# CRDC.net
KiCad netlist of a schematic drawn in EAGLE
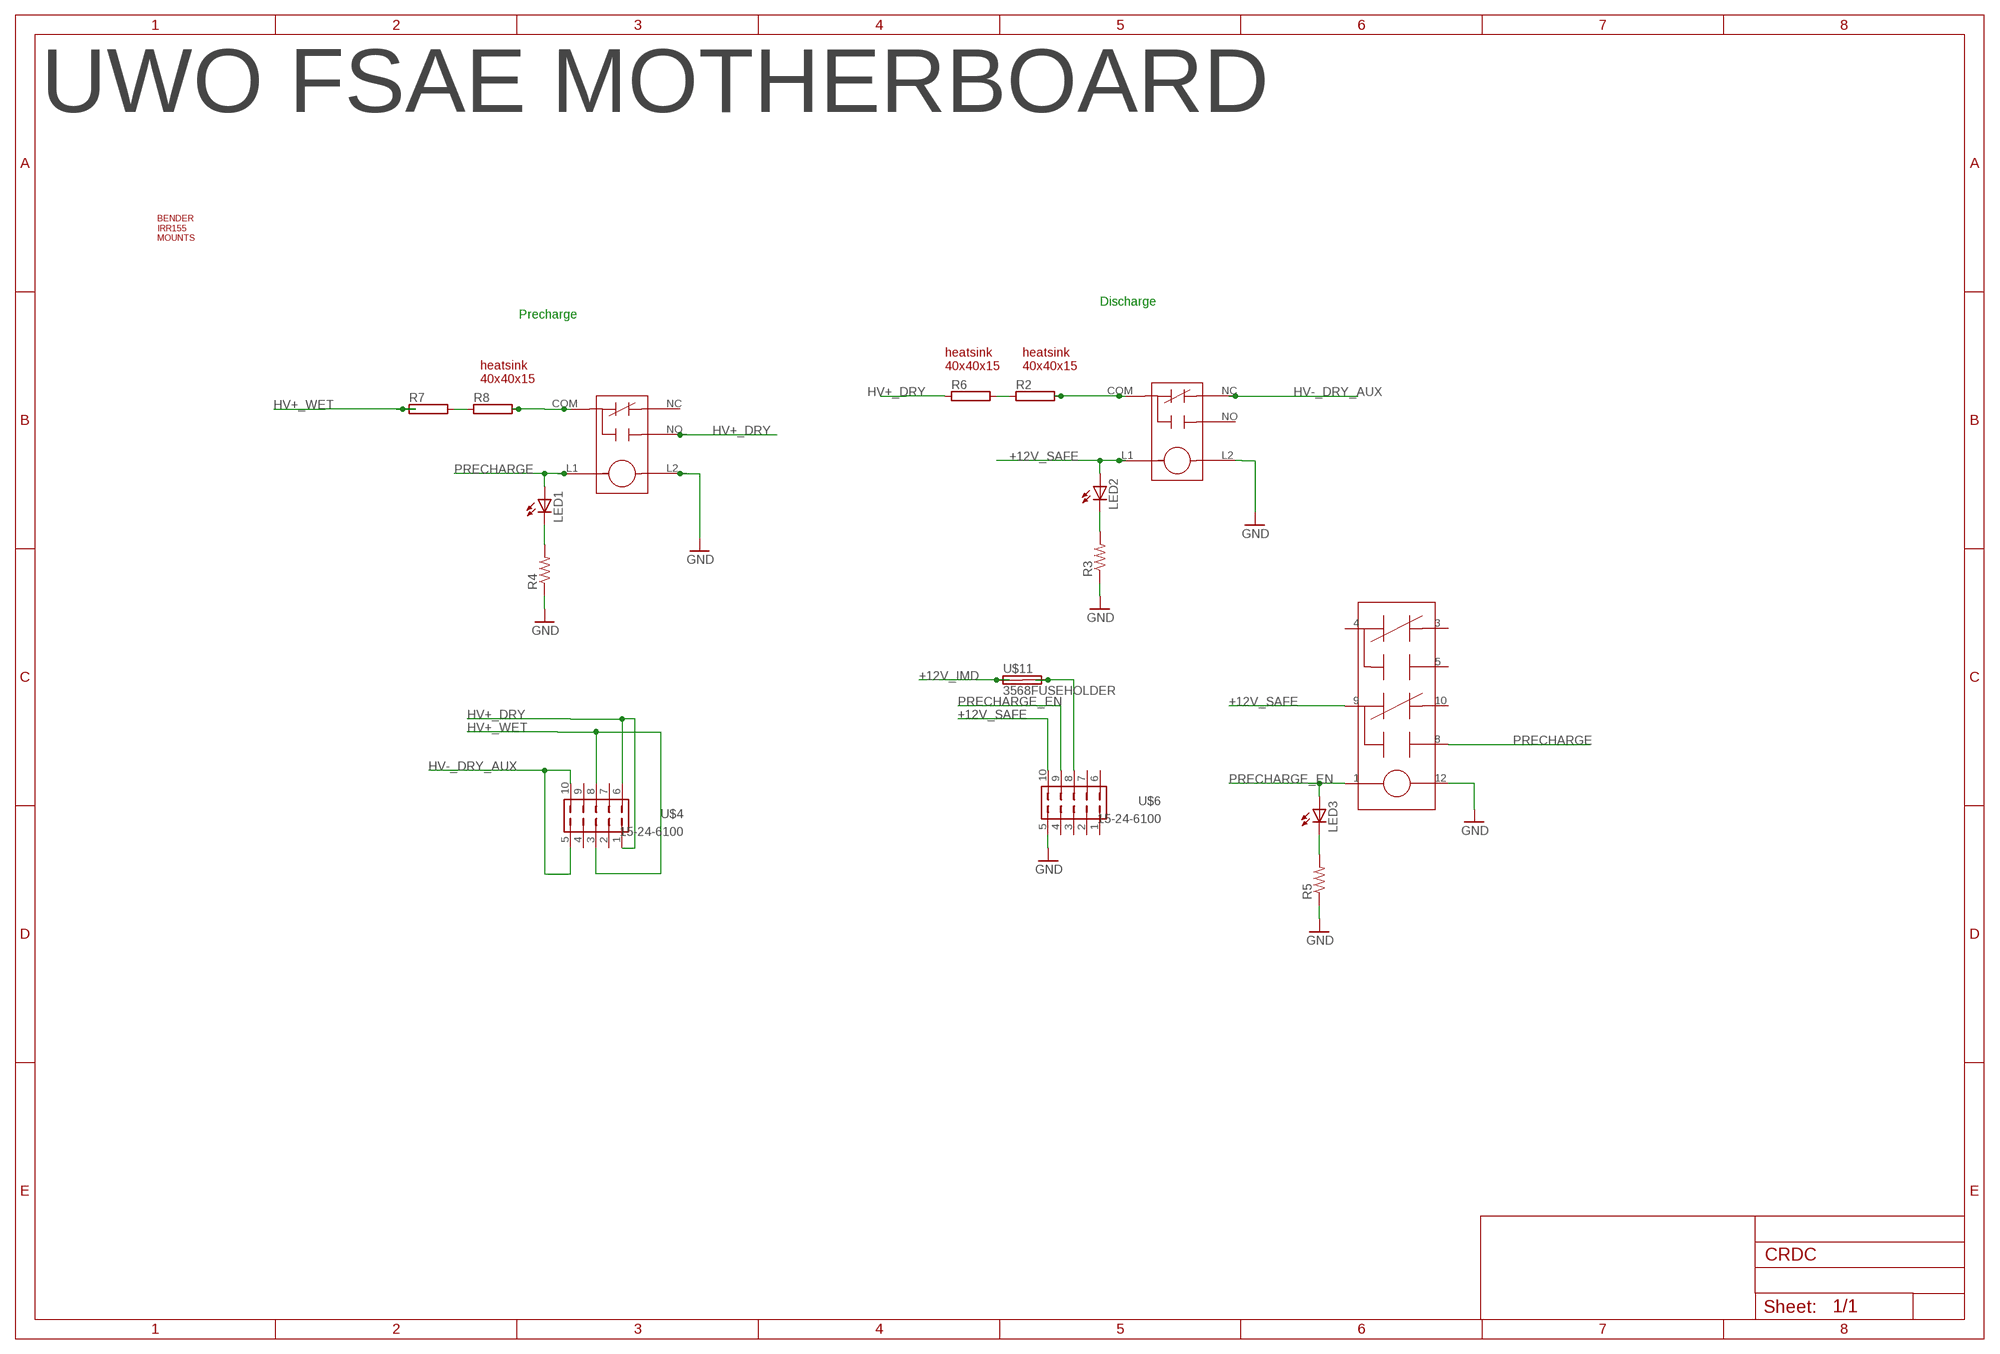
[diagram p0: schematic, sheet 1]

(export (version "E")
  (design (tool "Eeschema 10.0.6"))
  (components
    (comp (ref "LED1")
      (value "LED3MM")
      (footprint "eagle-import:LED3MM")
      (libsource (lib "eagle-import") (part "LED3MM"))
    )
    (comp (ref "LED2")
      (value "LED3MM")
      (footprint "eagle-import:LED3MM")
      (libsource (lib "eagle-import") (part "LED3MM"))
    )
    (comp (ref "LED3")
      (value "LED3MM")
      (footprint "eagle-import:LED3MM")
      (libsource (lib "eagle-import") (part "LED3MM"))
    )
    (comp (ref "R2")
      (value "RMG100-H")
      (footprint "eagle-import:TO-247-2H")
      (libsource (lib "eagle-import") (part "RMG100-H"))
    )
    (comp (ref "R3")
      (value "R-US_R0805")
      (footprint "eagle-import:R0805")
      (libsource (lib "eagle-import") (part "R-US_R0805"))
    )
    (comp (ref "R4")
      (value "R-US_R0805")
      (footprint "eagle-import:R0805")
      (libsource (lib "eagle-import") (part "R-US_R0805"))
    )
    (comp (ref "R5")
      (value "R-US_R0805")
      (footprint "eagle-import:R0805")
      (libsource (lib "eagle-import") (part "R-US_R0805"))
    )
    (comp (ref "R6")
      (value "RMG100-H")
      (footprint "eagle-import:TO-247-2H")
      (libsource (lib "eagle-import") (part "RMG100-H"))
    )
    (comp (ref "R7")
      (value "RMG100-H")
      (footprint "eagle-import:TO-247-2H")
      (libsource (lib "eagle-import") (part "RMG100-H"))
    )
    (comp (ref "R8")
      (value "RMG100-H")
      (footprint "eagle-import:TO-247-2H")
      (libsource (lib "eagle-import") (part "RMG100-H"))
    )
    (comp (ref "U$1")
      (value "G81C335")
      (footprint "eagle-import:G81C335")
      (libsource (lib "eagle-import") (part "G81C335"))
    )
    (comp (ref "U$2")
      (value "G81C335")
      (footprint "eagle-import:G81C335")
      (libsource (lib "eagle-import") (part "G81C335"))
    )
    (comp (ref "U$4")
      (value "15-24-6100")
      (footprint "eagle-import:15-24-6100")
      (libsource (lib "eagle-import") (part "15-24-6100"))
    )
    (comp (ref "U$5")
      (value "HEATSINK40X40X15")
      (footprint "eagle-import:HEATSINK40X40X15")
      (libsource (lib "eagle-import") (part "HEATSINK40X40X15"))
    )
    (comp (ref "U$6")
      (value "15-24-6100")
      (footprint "eagle-import:15-24-6100")
      (libsource (lib "eagle-import") (part "15-24-6100"))
    )
    (comp (ref "U$7")
      (value "V23079B1203B301")
      (footprint "eagle-import:V23079B1203B301")
      (libsource (lib "eagle-import") (part "V23079B1203B301"))
    )
    (comp (ref "U$8")
      (value "HEATSINK40X40X15")
      (footprint "eagle-import:HEATSINK40X40X15")
      (libsource (lib "eagle-import") (part "HEATSINK40X40X15"))
    )
    (comp (ref "U$9")
      (value "HEATSINK40X40X15")
      (footprint "eagle-import:HEATSINK40X40X15")
      (libsource (lib "eagle-import") (part "HEATSINK40X40X15"))
    )
    (comp (ref "U$10")
      (value "BENDER_IRR155")
      (footprint "eagle-import:BENDER_IRR155")
      (libsource (lib "eagle-import") (part "BENDER_IRR155"))
    )
    (comp (ref "U$11")
      (value "3568FUSEHOLDER")
      (footprint "eagle-import:3568")
      (libsource (lib "eagle-import") (part "3568FUSEHOLDER"))
    )
  )
  (nets
    (net (code "1") (name "/+12V_IMD") (class "Default")
      (node (ref "U$11") (pin "L1") (pinfunction "1A_L1") (pintype "passive"))
      (node (ref "U$11") (pin "L2") (pinfunction "1B_L2") (pintype "passive"))
    )
    (net (code "2") (name "/+12V_SAFE") (class "Default")
      (node (ref "LED2") (pin "A") (pinfunction "A_A") (pintype "passive"))
      (node (ref "U$2") (pin "L1") (pinfunction "L1_L1") (pintype "bidirectional"))
      (node (ref "U$6") (pin "10") (pinfunction "10_10") (pintype "passive"))
      (node (ref "U$7") (pin "9") (pinfunction "9_9") (pintype "bidirectional"))
    )
    (net (code "3") (name "/HV+_DRY") (class "Default")
      (node (ref "R6") (pin "1") (pinfunction "1_1") (pintype "passive"))
      (node (ref "U$1") (pin "NO") (pinfunction "NO_NO") (pintype "bidirectional"))
      (node (ref "U$4") (pin "1") (pinfunction "1_1") (pintype "passive"))
      (node (ref "U$4") (pin "6") (pinfunction "6_6") (pintype "passive"))
    )
    (net (code "4") (name "/HV+_WET") (class "Default")
      (node (ref "R7") (pin "1") (pinfunction "1_1") (pintype "passive"))
      (node (ref "U$4") (pin "3") (pinfunction "3_3") (pintype "passive"))
      (node (ref "U$4") (pin "8") (pinfunction "8_8") (pintype "passive"))
    )
    (net (code "5") (name "/HV-_DRY_AUX") (class "Default")
      (node (ref "U$2") (pin "NC") (pinfunction "NC_NC") (pintype "bidirectional"))
      (node (ref "U$4") (pin "10") (pinfunction "10_10") (pintype "passive"))
      (node (ref "U$4") (pin "5") (pinfunction "5_5") (pintype "passive"))
    )
    (net (code "6") (name "/PRECHARGE") (class "Default")
      (node (ref "LED1") (pin "A") (pinfunction "A_A") (pintype "passive"))
      (node (ref "U$1") (pin "L1") (pinfunction "L1_L1") (pintype "bidirectional"))
      (node (ref "U$7") (pin "8") (pinfunction "8_8") (pintype "bidirectional"))
    )
    (net (code "7") (name "/PRECHARGE_EN") (class "Default")
      (node (ref "LED3") (pin "A") (pinfunction "A_A") (pintype "passive"))
      (node (ref "U$6") (pin "9") (pinfunction "9_9") (pintype "passive"))
      (node (ref "U$7") (pin "1") (pinfunction "1_1") (pintype "bidirectional"))
    )
    (net (code "8") (name "GND") (class "Default")
      (node (ref "R3") (pin "1") (pinfunction "1_1") (pintype "passive"))
      (node (ref "R4") (pin "1") (pinfunction "1_1") (pintype "passive"))
      (node (ref "R5") (pin "1") (pinfunction "1_1") (pintype "passive"))
      (node (ref "U$1") (pin "L2") (pinfunction "L2_L2") (pintype "bidirectional"))
      (node (ref "U$2") (pin "L2") (pinfunction "L2_L2") (pintype "bidirectional"))
      (node (ref "U$6") (pin "5") (pinfunction "5_5") (pintype "passive"))
      (node (ref "U$7") (pin "12") (pinfunction "12_12") (pintype "bidirectional"))
    )
    (net (code "9") (name "Net-(LED1-C)") (class "Default")
      (node (ref "LED1") (pin "K") (pinfunction "C_K") (pintype "passive"))
      (node (ref "R4") (pin "2") (pinfunction "2_2") (pintype "passive"))
    )
    (net (code "10") (name "Net-(LED2-C)") (class "Default")
      (node (ref "LED2") (pin "K") (pinfunction "C_K") (pintype "passive"))
      (node (ref "R3") (pin "2") (pinfunction "2_2") (pintype "passive"))
    )
    (net (code "11") (name "Net-(LED3-C)") (class "Default")
      (node (ref "LED3") (pin "K") (pinfunction "C_K") (pintype "passive"))
      (node (ref "R5") (pin "2") (pinfunction "2_2") (pintype "passive"))
    )
    (net (code "12") (name "Net-(R2-Pad1)") (class "Default")
      (node (ref "R2") (pin "1") (pinfunction "1_1") (pintype "passive"))
      (node (ref "R6") (pin "2") (pinfunction "2_2") (pintype "passive"))
    )
    (net (code "13") (name "Net-(R2-Pad2)") (class "Default")
      (node (ref "R2") (pin "2") (pinfunction "2_2") (pintype "passive"))
      (node (ref "U$2") (pin "COM") (pinfunction "COM_COM") (pintype "bidirectional"))
    )
    (net (code "14") (name "Net-(R7-Pad2)") (class "Default")
      (node (ref "R7") (pin "2") (pinfunction "2_2") (pintype "passive"))
      (node (ref "R8") (pin "1") (pinfunction "1_1") (pintype "passive"))
    )
    (net (code "15") (name "Net-(R8-Pad2)") (class "Default")
      (node (ref "R8") (pin "2") (pinfunction "2_2") (pintype "passive"))
      (node (ref "U$1") (pin "COM") (pinfunction "COM_COM") (pintype "bidirectional"))
    )
    (net (code "16") (name "Net-(U$11-2A)") (class "Default")
      (node (ref "U$11") (pin "R1") (pinfunction "2A_R1") (pintype "passive"))
      (node (ref "U$11") (pin "R2") (pinfunction "2B_R2") (pintype "passive"))
      (node (ref "U$6") (pin "8") (pinfunction "8_8") (pintype "passive"))
    )
    (net (code "17") (name "unconnected-(U$1-PadNC)") (class "Default")
      (node (ref "U$1") (pin "NC") (pinfunction "NC_NC") (pintype "bidirectional"))
    )
    (net (code "18") (name "unconnected-(U$2-PadNO)") (class "Default")
      (node (ref "U$2") (pin "NO") (pinfunction "NO_NO") (pintype "bidirectional"))
    )
    (net (code "19") (name "unconnected-(U$4-Pad2)") (class "Default")
      (node (ref "U$4") (pin "2") (pinfunction "2_2") (pintype "passive"))
    )
    (net (code "20") (name "unconnected-(U$4-Pad4)") (class "Default")
      (node (ref "U$4") (pin "4") (pinfunction "4_4") (pintype "passive"))
    )
    (net (code "21") (name "unconnected-(U$4-Pad7)") (class "Default")
      (node (ref "U$4") (pin "7") (pinfunction "7_7") (pintype "passive"))
    )
    (net (code "22") (name "unconnected-(U$4-Pad9)") (class "Default")
      (node (ref "U$4") (pin "9") (pinfunction "9_9") (pintype "passive"))
    )
    (net (code "23") (name "unconnected-(U$6-Pad1)") (class "Default")
      (node (ref "U$6") (pin "1") (pinfunction "1_1") (pintype "passive"))
    )
    (net (code "24") (name "unconnected-(U$6-Pad2)") (class "Default")
      (node (ref "U$6") (pin "2") (pinfunction "2_2") (pintype "passive"))
    )
    (net (code "25") (name "unconnected-(U$6-Pad3)") (class "Default")
      (node (ref "U$6") (pin "3") (pinfunction "3_3") (pintype "passive"))
    )
    (net (code "26") (name "unconnected-(U$6-Pad4)") (class "Default")
      (node (ref "U$6") (pin "4") (pinfunction "4_4") (pintype "passive"))
    )
    (net (code "27") (name "unconnected-(U$6-Pad6)") (class "Default")
      (node (ref "U$6") (pin "6") (pinfunction "6_6") (pintype "passive"))
    )
    (net (code "28") (name "unconnected-(U$6-Pad7)") (class "Default")
      (node (ref "U$6") (pin "7") (pinfunction "7_7") (pintype "passive"))
    )
    (net (code "29") (name "unconnected-(U$7-Pad3)") (class "Default")
      (node (ref "U$7") (pin "3") (pinfunction "3_3") (pintype "bidirectional"))
    )
    (net (code "30") (name "unconnected-(U$7-Pad4)") (class "Default")
      (node (ref "U$7") (pin "4") (pinfunction "4_4") (pintype "bidirectional"))
    )
    (net (code "31") (name "unconnected-(U$7-Pad5)") (class "Default")
      (node (ref "U$7") (pin "5") (pinfunction "5_5") (pintype "bidirectional"))
    )
    (net (code "32") (name "unconnected-(U$7-Pad10)") (class "Default")
      (node (ref "U$7") (pin "10") (pinfunction "10_10") (pintype "bidirectional"))
    )
  )
)
